# Schematics.net
KiCad netlist of a schematic drawn in Altium Designer
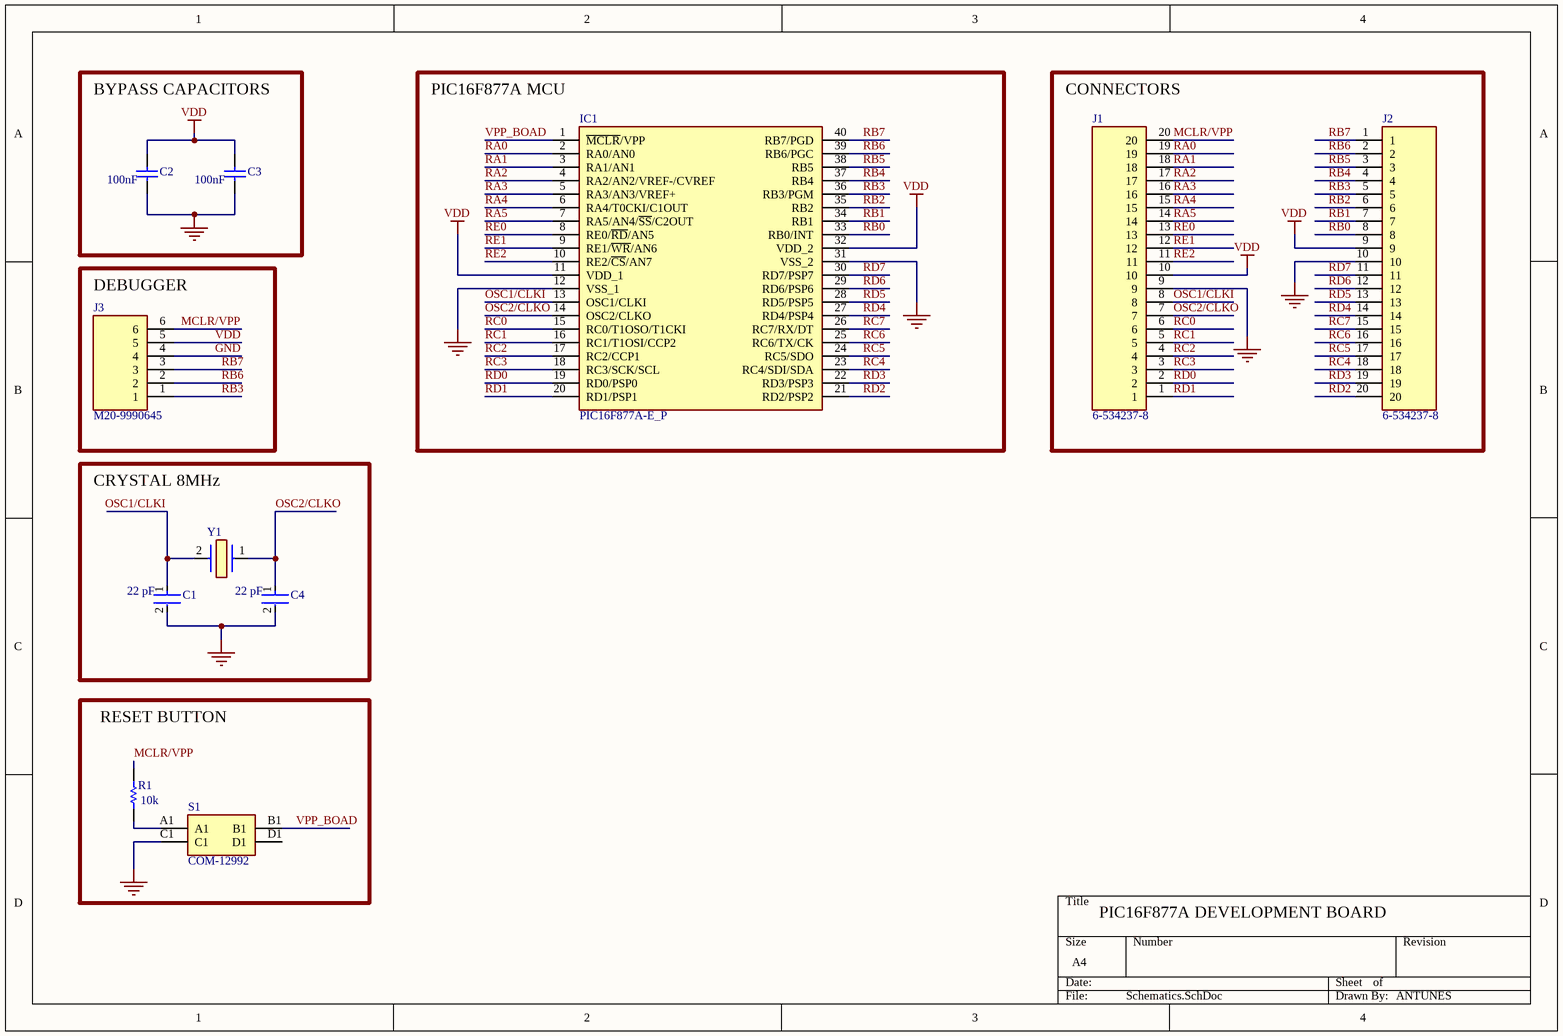
[diagram p0: Schematics.SchDoc]

(export (version "E")
  (design (tool "Eeschema 10.0.6"))
  (components
    (comp (ref "C1")
      (value "22 pF")
      (footprint "FP-C0805C-DN-MFG")
      (description "CAP CER 22PF 100V 5% NP0 0805")
      (fields
        (field (name "OCTOPART") "https://octopart.com/c0805c220j1gactu-kemet-3791395")
        (field (name "TOLERANCE") "0.05")
      )
      (libsource (lib "Altium Content Vault") (part "b4654b650e69147ec39a6b967a45e02"))
    )
    (comp (ref "C2")
      (value "100nF")
      (footprint "CAPC2013X94X50LL20T25")
      (fields
        (field (name "MANUFACTURER") "AVX Interconnect / Elco")
        (field (name "PART NUMBER") "08055C104JAZ2A")
      )
      (libsource (lib "Altium Content Vault") (part "CAP"))
    )
    (comp (ref "C3")
      (value "100nF")
      (footprint "CAPC2013X94X50LL20T25")
      (fields
        (field (name "MANUFACTURER") "AVX Interconnect / Elco")
        (field (name "PART NUMBER") "08055C104JAZ2A")
      )
      (libsource (lib "Altium Content Vault") (part "CAP"))
    )
    (comp (ref "C4")
      (value "22 pF")
      (footprint "FP-C0805C-DN-MFG")
      (description "CAP CER 22PF 100V 5% NP0 0805")
      (fields
        (field (name "OCTOPART") "https://octopart.com/c0805c220j1gactu-kemet-3791395")
        (field (name "TOLERANCE") "0.05")
      )
      (libsource (lib "Altium Content Vault") (part "b4654b650e69147ec39a6b967a45e02"))
    )
    (comp (ref "IC1")
      (value "PIC16F877A-E_P")
      (footprint "My_lib:DIP1550W56P254L5219H483Q40N")
      (description "Integrated Circuit")
      (fields
        (field (name "MANUFACTURER_PART_NUMBER") "PIC16F877A-E/P")
        (field (name "MOUSER PART NUMBER") "579-PIC16F877A-E/P")
      )
      (libsource (lib "My_lib") (part "PIC16F877A-E_P"))
    )
    (comp (ref "J1")
      (value "6-534237-8")
      (footprint "My_lib:RHDR20W76P0X254_1X20_5080X356X889P")
      (description "Connector")
      (fields (field (name "MOUSER PART NUMBER") "571-6-534237-8"))
      (libsource (lib "") (part "6-534237-8_1"))
    )
    (comp (ref "J2")
      (value "6-534237-8")
      (footprint "My_lib:RHDR20W76P0X254_1X20_5080X356X889P")
      (description "Connector")
      (fields (field (name "MOUSER PART NUMBER") "571-6-534237-8"))
      (libsource (lib "My_lib") (part "6-534237-8"))
    )
    (comp (ref "J3")
      (value "M20-9990645")
      (footprint "My_lib:HDRV6W66P0X254_1X6_1524X254X874P")
      (description "Connector")
      (fields (field (name "MOUSER PART NUMBER") "855-M20-9990645"))
      (libsource (lib "My_lib") (part "M20-9990645"))
    )
    (comp (ref "R1")
      (value "10k")
      (footprint "RESC2013X60X35NL10T20")
      (description "Chip Resistor, 10 KOhm, +/- 1%, 0.125 W, -55 to 155 degC, 0805 (2012 Metric), RoHS, Tape and Reel")
      (fields (field (name "MANUFACTURER") "Yageo") (field (name "Comment") "RC0805FR-0710KL"))
      (libsource (lib "Altium Content Vault") (part "RES-2"))
    )
    (comp (ref "S1")
      (value "COM-12992")
      (footprint "My_lib:COM12992")
      (description "Switch")
      (fields (field (name "MOUSER PART NUMBER") "474-COM-12992"))
      (libsource (lib "My_lib") (part "COM-12992"))
    )
    (comp (ref "Y1")
      (value "LFXTAL030234Reel")
      (footprint "My_lib:LFXTAL030234Reel")
      (description "Crystal or Oscillator")
      (fields
        (field (name "MOUSER PART NUMBER") "449-LFXTAL030234REEL")
        (field (name "ARROW PART NUMBER") "LFXTAL030234REEL")
      )
      (libsource (lib "My_lib") (part "LFXTAL030234Reel"))
    )
  )
  (nets
    (net (code "1") (name "/MCLR{slash}VPP") (class "Default")
      (node (ref "J1") (pin "20") (pinfunction "20_20") (pintype "passive"))
      (node (ref "J3") (pin "6") (pinfunction "6_6") (pintype "passive"))
      (node (ref "R1") (pin "2") (pinfunction "2_2") (pintype "passive"))
    )
    (net (code "2") (name "/OSC1{slash}CLKI") (class "Default")
      (node (ref "C1") (pin "1") (pinfunction "1_1") (pintype "passive"))
      (node (ref "IC1") (pin "13") (pinfunction "OSC1/CLKI_13") (pintype "passive"))
      (node (ref "J1") (pin "8") (pinfunction "8_8") (pintype "passive"))
      (node (ref "Y1") (pin "2") (pinfunction "CRYSTAL_2_2") (pintype "passive"))
    )
    (net (code "3") (name "/OSC2{slash}CLKO") (class "Default")
      (node (ref "C4") (pin "1") (pinfunction "1_1") (pintype "passive"))
      (node (ref "IC1") (pin "14") (pinfunction "OSC2/CLKO_14") (pintype "passive"))
      (node (ref "J1") (pin "7") (pinfunction "7_7") (pintype "passive"))
      (node (ref "Y1") (pin "1") (pinfunction "CRYSTAL_1_1") (pintype "passive"))
    )
    (net (code "4") (name "/RA0") (class "Default")
      (node (ref "IC1") (pin "2") (pinfunction "RA0/AN0_2") (pintype "passive"))
      (node (ref "J1") (pin "19") (pinfunction "19_19") (pintype "passive"))
    )
    (net (code "5") (name "/RA1") (class "Default")
      (node (ref "IC1") (pin "3") (pinfunction "RA1/AN1_3") (pintype "passive"))
      (node (ref "J1") (pin "18") (pinfunction "18_18") (pintype "passive"))
    )
    (net (code "6") (name "/RA2") (class "Default")
      (node (ref "IC1") (pin "4") (pinfunction "RA2/AN2/VREF-/CVREF_4") (pintype "passive"))
      (node (ref "J1") (pin "17") (pinfunction "17_17") (pintype "passive"))
    )
    (net (code "7") (name "/RA3") (class "Default")
      (node (ref "IC1") (pin "5") (pinfunction "RA3/AN3/VREF+_5") (pintype "passive"))
      (node (ref "J1") (pin "16") (pinfunction "16_16") (pintype "passive"))
    )
    (net (code "8") (name "/RA4") (class "Default")
      (node (ref "IC1") (pin "6") (pinfunction "RA4/T0CKI/C1OUT_6") (pintype "passive"))
      (node (ref "J1") (pin "15") (pinfunction "15_15") (pintype "passive"))
    )
    (net (code "9") (name "/RA5") (class "Default")
      (node (ref "IC1") (pin "7") (pinfunction "RA5/AN4/~{SS}/C2OUT_7") (pintype "passive"))
      (node (ref "J1") (pin "14") (pinfunction "14_14") (pintype "passive"))
    )
    (net (code "10") (name "/RB0") (class "Default")
      (node (ref "IC1") (pin "33") (pinfunction "RB0/INT_33") (pintype "passive"))
      (node (ref "J2") (pin "8") (pinfunction "8_8") (pintype "passive"))
    )
    (net (code "11") (name "/RB1") (class "Default")
      (node (ref "IC1") (pin "34") (pinfunction "RB1_34") (pintype "passive"))
      (node (ref "J2") (pin "7") (pinfunction "7_7") (pintype "passive"))
    )
    (net (code "12") (name "/RB2") (class "Default")
      (node (ref "IC1") (pin "35") (pinfunction "RB2_35") (pintype "passive"))
      (node (ref "J2") (pin "6") (pinfunction "6_6") (pintype "passive"))
    )
    (net (code "13") (name "/RB3") (class "Default")
      (node (ref "IC1") (pin "36") (pinfunction "RB3/PGM_36") (pintype "passive"))
      (node (ref "J2") (pin "5") (pinfunction "5_5") (pintype "passive"))
      (node (ref "J3") (pin "1") (pinfunction "1_1") (pintype "passive"))
    )
    (net (code "14") (name "/RB4") (class "Default")
      (node (ref "IC1") (pin "37") (pinfunction "RB4_37") (pintype "passive"))
      (node (ref "J2") (pin "4") (pinfunction "4_4") (pintype "passive"))
    )
    (net (code "15") (name "/RB5") (class "Default")
      (node (ref "IC1") (pin "38") (pinfunction "RB5_38") (pintype "passive"))
      (node (ref "J2") (pin "3") (pinfunction "3_3") (pintype "passive"))
    )
    (net (code "16") (name "/RB6") (class "Default")
      (node (ref "IC1") (pin "39") (pinfunction "RB6/PGC_39") (pintype "passive"))
      (node (ref "J2") (pin "2") (pinfunction "2_2") (pintype "passive"))
      (node (ref "J3") (pin "2") (pinfunction "2_2") (pintype "passive"))
    )
    (net (code "17") (name "/RB7") (class "Default")
      (node (ref "IC1") (pin "40") (pinfunction "RB7/PGD_40") (pintype "passive"))
      (node (ref "J2") (pin "1") (pinfunction "1_1") (pintype "passive"))
      (node (ref "J3") (pin "3") (pinfunction "3_3") (pintype "passive"))
    )
    (net (code "18") (name "/RC0") (class "Default")
      (node (ref "IC1") (pin "15") (pinfunction "RC0/T1OSO/T1CKI_15") (pintype "passive"))
      (node (ref "J1") (pin "6") (pinfunction "6_6") (pintype "passive"))
    )
    (net (code "19") (name "/RC1") (class "Default")
      (node (ref "IC1") (pin "16") (pinfunction "RC1/T1OSI/CCP2_16") (pintype "passive"))
      (node (ref "J1") (pin "5") (pinfunction "5_5") (pintype "passive"))
    )
    (net (code "20") (name "/RC2") (class "Default")
      (node (ref "IC1") (pin "17") (pinfunction "RC2/CCP1_17") (pintype "passive"))
      (node (ref "J1") (pin "4") (pinfunction "4_4") (pintype "passive"))
    )
    (net (code "21") (name "/RC3") (class "Default")
      (node (ref "IC1") (pin "18") (pinfunction "RC3/SCK/SCL_18") (pintype "passive"))
      (node (ref "J1") (pin "3") (pinfunction "3_3") (pintype "passive"))
    )
    (net (code "22") (name "/RC4") (class "Default")
      (node (ref "IC1") (pin "23") (pinfunction "RC4/SDI/SDA_23") (pintype "passive"))
      (node (ref "J2") (pin "18") (pinfunction "18_18") (pintype "passive"))
    )
    (net (code "23") (name "/RC5") (class "Default")
      (node (ref "IC1") (pin "24") (pinfunction "RC5/SDO_24") (pintype "passive"))
      (node (ref "J2") (pin "17") (pinfunction "17_17") (pintype "passive"))
    )
    (net (code "24") (name "/RC6") (class "Default")
      (node (ref "IC1") (pin "25") (pinfunction "RC6/TX/CK_25") (pintype "passive"))
      (node (ref "J2") (pin "16") (pinfunction "16_16") (pintype "passive"))
    )
    (net (code "25") (name "/RC7") (class "Default")
      (node (ref "IC1") (pin "26") (pinfunction "RC7/RX/DT_26") (pintype "passive"))
      (node (ref "J2") (pin "15") (pinfunction "15_15") (pintype "passive"))
    )
    (net (code "26") (name "/RD0") (class "Default")
      (node (ref "IC1") (pin "19") (pinfunction "RD0/PSP0_19") (pintype "passive"))
      (node (ref "J1") (pin "2") (pinfunction "2_2") (pintype "passive"))
    )
    (net (code "27") (name "/RD1") (class "Default")
      (node (ref "IC1") (pin "20") (pinfunction "RD1/PSP1_20") (pintype "passive"))
      (node (ref "J1") (pin "1") (pinfunction "1_1") (pintype "passive"))
    )
    (net (code "28") (name "/RD2") (class "Default")
      (node (ref "IC1") (pin "21") (pinfunction "RD2/PSP2_21") (pintype "passive"))
      (node (ref "J2") (pin "20") (pinfunction "20_20") (pintype "passive"))
    )
    (net (code "29") (name "/RD3") (class "Default")
      (node (ref "IC1") (pin "22") (pinfunction "RD3/PSP3_22") (pintype "passive"))
      (node (ref "J2") (pin "19") (pinfunction "19_19") (pintype "passive"))
    )
    (net (code "30") (name "/RD4") (class "Default")
      (node (ref "IC1") (pin "27") (pinfunction "RD4/PSP4_27") (pintype "passive"))
      (node (ref "J2") (pin "14") (pinfunction "14_14") (pintype "passive"))
    )
    (net (code "31") (name "/RD5") (class "Default")
      (node (ref "IC1") (pin "28") (pinfunction "RD5/PSP5_28") (pintype "passive"))
      (node (ref "J2") (pin "13") (pinfunction "13_13") (pintype "passive"))
    )
    (net (code "32") (name "/RD6") (class "Default")
      (node (ref "IC1") (pin "29") (pinfunction "RD6/PSP6_29") (pintype "passive"))
      (node (ref "J2") (pin "12") (pinfunction "12_12") (pintype "passive"))
    )
    (net (code "33") (name "/RD7") (class "Default")
      (node (ref "IC1") (pin "30") (pinfunction "RD7/PSP7_30") (pintype "passive"))
      (node (ref "J2") (pin "11") (pinfunction "11_11") (pintype "passive"))
    )
    (net (code "34") (name "/RE0") (class "Default")
      (node (ref "IC1") (pin "8") (pinfunction "RE0/~{RD}/AN5_8") (pintype "passive"))
      (node (ref "J1") (pin "13") (pinfunction "13_13") (pintype "passive"))
    )
    (net (code "35") (name "/RE1") (class "Default")
      (node (ref "IC1") (pin "9") (pinfunction "RE1/~{WR}/AN6_9") (pintype "passive"))
      (node (ref "J1") (pin "12") (pinfunction "12_12") (pintype "passive"))
    )
    (net (code "36") (name "/RE2") (class "Default")
      (node (ref "IC1") (pin "10") (pinfunction "RE2/~{CS}/AN7_10") (pintype "passive"))
      (node (ref "J1") (pin "11") (pinfunction "11_11") (pintype "passive"))
    )
    (net (code "37") (name "/VPP_BOAD") (class "Default")
      (node (ref "IC1") (pin "1") (pinfunction "~{MCLR}/VPP_1") (pintype "passive"))
      (node (ref "S1") (pin "B1") (pinfunction "B1_B1") (pintype "passive"))
    )
    (net (code "38") (name "GND") (class "Default")
      (node (ref "C1") (pin "2") (pinfunction "2_2") (pintype "passive"))
      (node (ref "C2") (pin "1") (pinfunction "1_1") (pintype "passive"))
      (node (ref "C3") (pin "1") (pinfunction "1_1") (pintype "passive"))
      (node (ref "C4") (pin "2") (pinfunction "2_2") (pintype "passive"))
      (node (ref "IC1") (pin "12") (pinfunction "VSS_1_12") (pintype "passive"))
      (node (ref "IC1") (pin "31") (pinfunction "VSS_2_31") (pintype "passive"))
      (node (ref "J1") (pin "9") (pinfunction "9_9") (pintype "passive"))
      (node (ref "J2") (pin "10") (pinfunction "10_10") (pintype "passive"))
      (node (ref "J3") (pin "4") (pinfunction "4_4") (pintype "passive"))
      (node (ref "S1") (pin "C1") (pinfunction "C1_C1") (pintype "passive"))
    )
    (net (code "39") (name "Net-(R1-Pad1)") (class "Default")
      (node (ref "R1") (pin "1") (pinfunction "1_1") (pintype "passive"))
      (node (ref "S1") (pin "A1") (pinfunction "A1_A1") (pintype "passive"))
    )
    (net (code "40") (name "VDD") (class "Default")
      (node (ref "C2") (pin "2") (pinfunction "2_2") (pintype "passive"))
      (node (ref "C3") (pin "2") (pinfunction "2_2") (pintype "passive"))
      (node (ref "IC1") (pin "11") (pinfunction "VDD_1_11") (pintype "passive"))
      (node (ref "IC1") (pin "32") (pinfunction "VDD_2_32") (pintype "passive"))
      (node (ref "J1") (pin "10") (pinfunction "10_10") (pintype "passive"))
      (node (ref "J2") (pin "9") (pinfunction "9_9") (pintype "passive"))
      (node (ref "J3") (pin "5") (pinfunction "5_5") (pintype "passive"))
    )
    (net (code "41") (name "unconnected-(S1-PadD1)") (class "Default")
      (node (ref "S1") (pin "D1") (pinfunction "D1_D1") (pintype "passive"))
    )
  )
)
